# Mother_Board_ver2_0_0.net
KiCad netlist of a schematic drawn in EAGLE
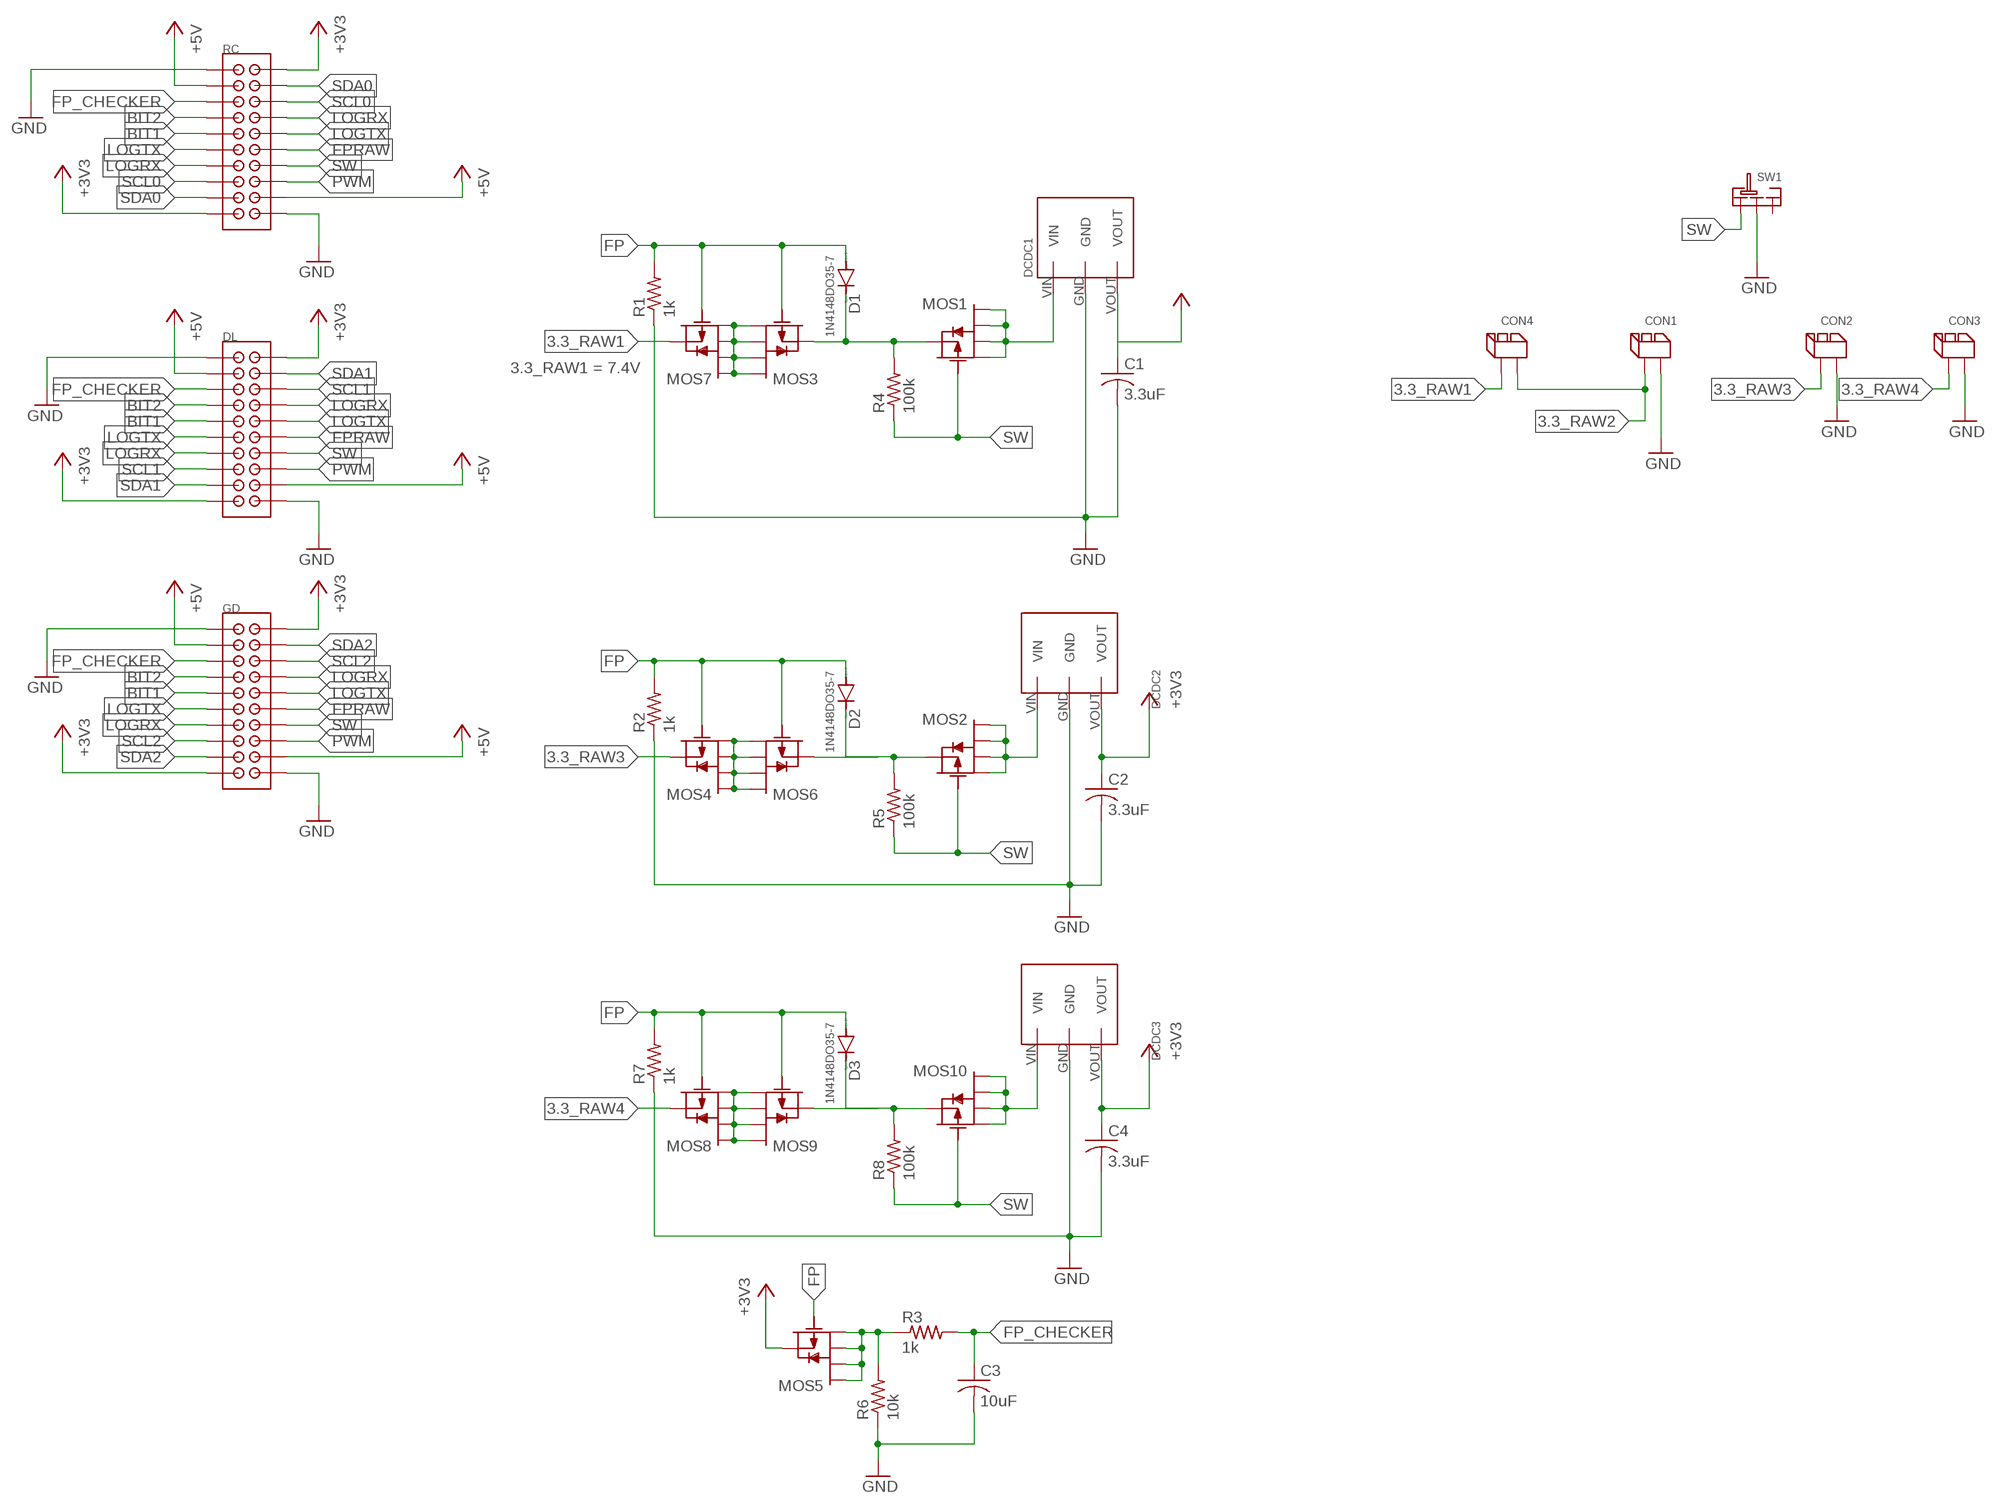
[diagram p0: schematic, sheet 1]

(export (version "E")
  (design (tool "Eeschema 10.0.6"))
  (components
    (comp (ref "C1")
      (value "3.3uF")
      (footprint "eagle-import:C0603")
      (libsource (lib "eagle-import") (part "C-USC0603"))
    )
    (comp (ref "C2")
      (value "3.3uF")
      (footprint "eagle-import:C0603")
      (libsource (lib "eagle-import") (part "C-USC0603"))
    )
    (comp (ref "C3")
      (value "10uF")
      (footprint "eagle-import:C0603")
      (libsource (lib "eagle-import") (part "C-USC0603"))
    )
    (comp (ref "C4")
      (value "3.3uF")
      (footprint "eagle-import:C0603")
      (libsource (lib "eagle-import") (part "C-USC0603"))
    )
    (comp (ref "CON1")
      (value "2PIN")
      (footprint "eagle-import:2PIN")
      (libsource (lib "eagle-import") (part "2PIN"))
    )
    (comp (ref "CON2")
      (value "2PIN")
      (footprint "eagle-import:2PIN")
      (libsource (lib "eagle-import") (part "2PIN"))
    )
    (comp (ref "CON3")
      (value "2PIN")
      (footprint "eagle-import:2PIN")
      (libsource (lib "eagle-import") (part "2PIN"))
    )
    (comp (ref "CON4")
      (value "2PIN")
      (footprint "eagle-import:2PIN")
      (libsource (lib "eagle-import") (part "2PIN"))
    )
    (comp (ref "D1")
      (value "1N4148DO35-7")
      (footprint "eagle-import:DO35-7")
      (libsource (lib "eagle-import") (part "1N4148DO35-7"))
    )
    (comp (ref "D2")
      (value "1N4148DO35-7")
      (footprint "eagle-import:DO35-7")
      (libsource (lib "eagle-import") (part "1N4148DO35-7"))
    )
    (comp (ref "D3")
      (value "1N4148DO35-7")
      (footprint "eagle-import:DO35-7")
      (libsource (lib "eagle-import") (part "1N4148DO35-7"))
    )
    (comp (ref "DCDC1")
      (value "5V1A_M78AR05-1")
      (footprint "eagle-import:5V1A_M78AR05-1")
      (libsource (lib "eagle-import") (part "5V1A_M78AR05-1"))
    )
    (comp (ref "DCDC2")
      (value "3.3V1A_M78AR033-1")
      (footprint "eagle-import:3.3V1A_M78AR033-1")
      (libsource (lib "eagle-import") (part "3.3V1A_M78AR033-1"))
    )
    (comp (ref "DCDC3")
      (value "3.3V1A_M78AR033-1")
      (footprint "eagle-import:3.3V1A_M78AR033-1")
      (libsource (lib "eagle-import") (part "3.3V1A_M78AR033-1"))
    )
    (comp (ref "DL")
      (value "2X10")
      (footprint "eagle-import:2X10")
      (libsource (lib "eagle-import") (part "2X10"))
    )
    (comp (ref "GD")
      (value "2X10")
      (footprint "eagle-import:2X10")
      (libsource (lib "eagle-import") (part "2X10"))
    )
    (comp (ref "MOS1")
      (value "PCH_SSM6J808R")
      (footprint "eagle-import:SSM6J808R")
      (libsource (lib "eagle-import") (part "PCH_SSM6J808R"))
    )
    (comp (ref "MOS2")
      (value "PCH_SSM6J808R")
      (footprint "eagle-import:SSM6J808R")
      (libsource (lib "eagle-import") (part "PCH_SSM6J808R"))
    )
    (comp (ref "MOS3")
      (value "PCH_SSM6J808R")
      (footprint "eagle-import:SSM6J808R")
      (libsource (lib "eagle-import") (part "PCH_SSM6J808R"))
    )
    (comp (ref "MOS4")
      (value "PCH_SSM6J808R")
      (footprint "eagle-import:SSM6J808R")
      (libsource (lib "eagle-import") (part "PCH_SSM6J808R"))
    )
    (comp (ref "MOS5")
      (value "PCH_SSM6J808R")
      (footprint "eagle-import:SSM6J808R")
      (libsource (lib "eagle-import") (part "PCH_SSM6J808R"))
    )
    (comp (ref "MOS6")
      (value "PCH_SSM6J808R")
      (footprint "eagle-import:SSM6J808R")
      (libsource (lib "eagle-import") (part "PCH_SSM6J808R"))
    )
    (comp (ref "MOS7")
      (value "PCH_SSM6J808R")
      (footprint "eagle-import:SSM6J808R")
      (libsource (lib "eagle-import") (part "PCH_SSM6J808R"))
    )
    (comp (ref "MOS8")
      (value "PCH_SSM6J808R")
      (footprint "eagle-import:SSM6J808R")
      (libsource (lib "eagle-import") (part "PCH_SSM6J808R"))
    )
    (comp (ref "MOS9")
      (value "PCH_SSM6J808R")
      (footprint "eagle-import:SSM6J808R")
      (libsource (lib "eagle-import") (part "PCH_SSM6J808R"))
    )
    (comp (ref "MOS10")
      (value "PCH_SSM6J808R")
      (footprint "eagle-import:SSM6J808R")
      (libsource (lib "eagle-import") (part "PCH_SSM6J808R"))
    )
    (comp (ref "R1")
      (value "1k")
      (footprint "eagle-import:R0603")
      (libsource (lib "eagle-import") (part "R-US_R0603"))
    )
    (comp (ref "R2")
      (value "1k")
      (footprint "eagle-import:R0603")
      (libsource (lib "eagle-import") (part "R-US_R0603"))
    )
    (comp (ref "R3")
      (value "1k")
      (footprint "eagle-import:R0603")
      (libsource (lib "eagle-import") (part "R-US_R0603"))
    )
    (comp (ref "R4")
      (value "100k")
      (footprint "eagle-import:R0603")
      (libsource (lib "eagle-import") (part "R-US_R0603"))
    )
    (comp (ref "R5")
      (value "100k")
      (footprint "eagle-import:R0603")
      (libsource (lib "eagle-import") (part "R-US_R0603"))
    )
    (comp (ref "R6")
      (value "10k")
      (footprint "eagle-import:R0603")
      (libsource (lib "eagle-import") (part "R-US_R0603"))
    )
    (comp (ref "R7")
      (value "1k")
      (footprint "eagle-import:R0603")
      (libsource (lib "eagle-import") (part "R-US_R0603"))
    )
    (comp (ref "R8")
      (value "100k")
      (footprint "eagle-import:R0603")
      (libsource (lib "eagle-import") (part "R-US_R0603"))
    )
    (comp (ref "RC")
      (value "2X10")
      (footprint "eagle-import:2X10")
      (libsource (lib "eagle-import") (part "2X10"))
    )
    (comp (ref "SW1")
      (value "SRIDE_SWITCH")
      (footprint "eagle-import:SRIDE_SWITCH")
      (libsource (lib "eagle-import") (part "SRIDE_SWITCH"))
    )
  )
  (nets
    (net (code "1") (name "+3V3") (class "Default")
      (node (ref "C2") (pin "1") (pinfunction "1_1") (pintype "passive"))
      (node (ref "C4") (pin "1") (pinfunction "1_1") (pintype "passive"))
      (node (ref "DCDC2") (pin "VOUT") (pinfunction "VOUT_VOUT") (pintype "bidirectional"))
      (node (ref "DCDC3") (pin "VOUT") (pinfunction "VOUT_VOUT") (pintype "bidirectional"))
      (node (ref "DL") (pin "P$19") (pinfunction "P$19_P$19") (pintype "bidirectional"))
      (node (ref "DL") (pin "P$2") (pinfunction "P$2_P$2") (pintype "bidirectional"))
      (node (ref "GD") (pin "P$19") (pinfunction "P$19_P$19") (pintype "bidirectional"))
      (node (ref "GD") (pin "P$2") (pinfunction "P$2_P$2") (pintype "bidirectional"))
      (node (ref "MOS5") (pin "4") (pinfunction "4_4") (pintype "bidirectional"))
      (node (ref "RC") (pin "P$19") (pinfunction "P$19_P$19") (pintype "bidirectional"))
      (node (ref "RC") (pin "P$2") (pinfunction "P$2_P$2") (pintype "bidirectional"))
    )
    (net (code "2") (name "+5V") (class "Default")
      (node (ref "C1") (pin "1") (pinfunction "1_1") (pintype "passive"))
      (node (ref "DCDC1") (pin "VOUT") (pinfunction "VOUT_VOUT") (pintype "bidirectional"))
      (node (ref "DL") (pin "P$18") (pinfunction "P$18_P$18") (pintype "bidirectional"))
      (node (ref "DL") (pin "P$3") (pinfunction "P$3_P$3") (pintype "bidirectional"))
      (node (ref "GD") (pin "P$18") (pinfunction "P$18_P$18") (pintype "bidirectional"))
      (node (ref "GD") (pin "P$3") (pinfunction "P$3_P$3") (pintype "bidirectional"))
      (node (ref "RC") (pin "P$18") (pinfunction "P$18_P$18") (pintype "bidirectional"))
      (node (ref "RC") (pin "P$3") (pinfunction "P$3_P$3") (pintype "bidirectional"))
    )
    (net (code "3") (name "3.3_RAW1") (class "Default")
      (node (ref "CON4") (pin "P$2") (pinfunction "P$2_P$2") (pintype "bidirectional"))
      (node (ref "MOS7") (pin "4") (pinfunction "4_4") (pintype "bidirectional"))
    )
    (net (code "4") (name "3.3_RAW2") (class "Default")
      (node (ref "CON1") (pin "P$2") (pinfunction "P$2_P$2") (pintype "bidirectional"))
      (node (ref "CON4") (pin "P$1") (pinfunction "P$1_P$1") (pintype "bidirectional"))
    )
    (net (code "5") (name "3.3_RAW3") (class "Default")
      (node (ref "CON2") (pin "P$2") (pinfunction "P$2_P$2") (pintype "bidirectional"))
      (node (ref "MOS4") (pin "4") (pinfunction "4_4") (pintype "bidirectional"))
    )
    (net (code "6") (name "3.3_RAW4") (class "Default")
      (node (ref "CON3") (pin "P$2") (pinfunction "P$2_P$2") (pintype "bidirectional"))
      (node (ref "MOS8") (pin "4") (pinfunction "4_4") (pintype "bidirectional"))
    )
    (net (code "7") (name "BIT1") (class "Default")
      (node (ref "DL") (pin "P$9") (pinfunction "P$9_P$9") (pintype "bidirectional"))
      (node (ref "GD") (pin "P$9") (pinfunction "P$9_P$9") (pintype "bidirectional"))
      (node (ref "RC") (pin "P$9") (pinfunction "P$9_P$9") (pintype "bidirectional"))
    )
    (net (code "8") (name "BIT2") (class "Default")
      (node (ref "DL") (pin "P$7") (pinfunction "P$7_P$7") (pintype "bidirectional"))
      (node (ref "GD") (pin "P$7") (pinfunction "P$7_P$7") (pintype "bidirectional"))
      (node (ref "RC") (pin "P$7") (pinfunction "P$7_P$7") (pintype "bidirectional"))
    )
    (net (code "9") (name "FP") (class "Default")
      (node (ref "D1") (pin "A") (pinfunction "A_A") (pintype "passive"))
      (node (ref "D2") (pin "A") (pinfunction "A_A") (pintype "passive"))
      (node (ref "D3") (pin "A") (pinfunction "A_A") (pintype "passive"))
      (node (ref "MOS3") (pin "3") (pinfunction "3_3") (pintype "bidirectional"))
      (node (ref "MOS4") (pin "3") (pinfunction "3_3") (pintype "bidirectional"))
      (node (ref "MOS5") (pin "3") (pinfunction "3_3") (pintype "bidirectional"))
      (node (ref "MOS6") (pin "3") (pinfunction "3_3") (pintype "bidirectional"))
      (node (ref "MOS7") (pin "3") (pinfunction "3_3") (pintype "bidirectional"))
      (node (ref "MOS8") (pin "3") (pinfunction "3_3") (pintype "bidirectional"))
      (node (ref "MOS9") (pin "3") (pinfunction "3_3") (pintype "bidirectional"))
      (node (ref "R1") (pin "2") (pinfunction "2_2") (pintype "passive"))
      (node (ref "R2") (pin "2") (pinfunction "2_2") (pintype "passive"))
      (node (ref "R7") (pin "2") (pinfunction "2_2") (pintype "passive"))
    )
    (net (code "10") (name "FPRAW") (class "Default")
      (node (ref "DL") (pin "P$12") (pinfunction "P$12_P$12") (pintype "bidirectional"))
      (node (ref "GD") (pin "P$12") (pinfunction "P$12_P$12") (pintype "bidirectional"))
      (node (ref "RC") (pin "P$12") (pinfunction "P$12_P$12") (pintype "bidirectional"))
    )
    (net (code "11") (name "FP_CHECKER") (class "Default")
      (node (ref "C3") (pin "1") (pinfunction "1_1") (pintype "passive"))
      (node (ref "DL") (pin "P$5") (pinfunction "P$5_P$5") (pintype "bidirectional"))
      (node (ref "GD") (pin "P$5") (pinfunction "P$5_P$5") (pintype "bidirectional"))
      (node (ref "R3") (pin "2") (pinfunction "2_2") (pintype "passive"))
      (node (ref "RC") (pin "P$5") (pinfunction "P$5_P$5") (pintype "bidirectional"))
    )
    (net (code "12") (name "GND") (class "Default")
      (node (ref "C1") (pin "2") (pinfunction "2_2") (pintype "passive"))
      (node (ref "C2") (pin "2") (pinfunction "2_2") (pintype "passive"))
      (node (ref "C3") (pin "2") (pinfunction "2_2") (pintype "passive"))
      (node (ref "C4") (pin "2") (pinfunction "2_2") (pintype "passive"))
      (node (ref "CON1") (pin "P$1") (pinfunction "P$1_P$1") (pintype "bidirectional"))
      (node (ref "CON2") (pin "P$1") (pinfunction "P$1_P$1") (pintype "bidirectional"))
      (node (ref "CON3") (pin "P$1") (pinfunction "P$1_P$1") (pintype "bidirectional"))
      (node (ref "DCDC1") (pin "GND") (pinfunction "GND_GND") (pintype "bidirectional"))
      (node (ref "DCDC2") (pin "GND") (pinfunction "GND_GND") (pintype "bidirectional"))
      (node (ref "DCDC3") (pin "GND") (pinfunction "GND_GND") (pintype "bidirectional"))
      (node (ref "DL") (pin "P$1") (pinfunction "P$1_P$1") (pintype "bidirectional"))
      (node (ref "DL") (pin "P$20") (pinfunction "P$20_P$20") (pintype "bidirectional"))
      (node (ref "GD") (pin "P$1") (pinfunction "P$1_P$1") (pintype "bidirectional"))
      (node (ref "GD") (pin "P$20") (pinfunction "P$20_P$20") (pintype "bidirectional"))
      (node (ref "R1") (pin "1") (pinfunction "1_1") (pintype "passive"))
      (node (ref "R2") (pin "1") (pinfunction "1_1") (pintype "passive"))
      (node (ref "R6") (pin "1") (pinfunction "1_1") (pintype "passive"))
      (node (ref "R7") (pin "1") (pinfunction "1_1") (pintype "passive"))
      (node (ref "RC") (pin "P$1") (pinfunction "P$1_P$1") (pintype "bidirectional"))
      (node (ref "RC") (pin "P$20") (pinfunction "P$20_P$20") (pintype "bidirectional"))
      (node (ref "SW1") (pin "LR") (pinfunction "LR_LR") (pintype "bidirectional"))
    )
    (net (code "13") (name "LOGRX") (class "Default")
      (node (ref "DL") (pin "P$13") (pinfunction "P$13_P$13") (pintype "bidirectional"))
      (node (ref "DL") (pin "P$8") (pinfunction "P$8_P$8") (pintype "bidirectional"))
      (node (ref "GD") (pin "P$13") (pinfunction "P$13_P$13") (pintype "bidirectional"))
      (node (ref "GD") (pin "P$8") (pinfunction "P$8_P$8") (pintype "bidirectional"))
      (node (ref "RC") (pin "P$13") (pinfunction "P$13_P$13") (pintype "bidirectional"))
      (node (ref "RC") (pin "P$8") (pinfunction "P$8_P$8") (pintype "bidirectional"))
    )
    (net (code "14") (name "LOGTX") (class "Default")
      (node (ref "DL") (pin "P$10") (pinfunction "P$10_P$10") (pintype "bidirectional"))
      (node (ref "DL") (pin "P$11") (pinfunction "P$11_P$11") (pintype "bidirectional"))
      (node (ref "GD") (pin "P$10") (pinfunction "P$10_P$10") (pintype "bidirectional"))
      (node (ref "GD") (pin "P$11") (pinfunction "P$11_P$11") (pintype "bidirectional"))
      (node (ref "RC") (pin "P$10") (pinfunction "P$10_P$10") (pintype "bidirectional"))
      (node (ref "RC") (pin "P$11") (pinfunction "P$11_P$11") (pintype "bidirectional"))
    )
    (net (code "15") (name "Net-(D1-PadC)") (class "Default")
      (node (ref "D1") (pin "C") (pinfunction "C_C") (pintype "passive"))
      (node (ref "MOS1") (pin "4") (pinfunction "4_4") (pintype "bidirectional"))
      (node (ref "MOS3") (pin "4") (pinfunction "4_4") (pintype "bidirectional"))
      (node (ref "R4") (pin "2") (pinfunction "2_2") (pintype "passive"))
    )
    (net (code "16") (name "Net-(D2-PadC)") (class "Default")
      (node (ref "D2") (pin "C") (pinfunction "C_C") (pintype "passive"))
      (node (ref "MOS2") (pin "4") (pinfunction "4_4") (pintype "bidirectional"))
      (node (ref "MOS6") (pin "4") (pinfunction "4_4") (pintype "bidirectional"))
      (node (ref "R5") (pin "2") (pinfunction "2_2") (pintype "passive"))
    )
    (net (code "17") (name "Net-(D3-PadC)") (class "Default")
      (node (ref "D3") (pin "C") (pinfunction "C_C") (pintype "passive"))
      (node (ref "MOS10") (pin "4") (pinfunction "4_4") (pintype "bidirectional"))
      (node (ref "MOS9") (pin "4") (pinfunction "4_4") (pintype "bidirectional"))
      (node (ref "R8") (pin "2") (pinfunction "2_2") (pintype "passive"))
    )
    (net (code "18") (name "Net-(DCDC1-PadVIN)") (class "Default")
      (node (ref "DCDC1") (pin "VIN") (pinfunction "VIN_VIN") (pintype "bidirectional"))
      (node (ref "MOS1") (pin "1") (pinfunction "1_1") (pintype "bidirectional"))
      (node (ref "MOS1") (pin "2") (pinfunction "2_2") (pintype "bidirectional"))
      (node (ref "MOS1") (pin "5") (pinfunction "5_5") (pintype "bidirectional"))
      (node (ref "MOS1") (pin "6") (pinfunction "6_6") (pintype "bidirectional"))
    )
    (net (code "19") (name "Net-(DCDC2-PadVIN)") (class "Default")
      (node (ref "DCDC2") (pin "VIN") (pinfunction "VIN_VIN") (pintype "bidirectional"))
      (node (ref "MOS2") (pin "1") (pinfunction "1_1") (pintype "bidirectional"))
      (node (ref "MOS2") (pin "2") (pinfunction "2_2") (pintype "bidirectional"))
      (node (ref "MOS2") (pin "5") (pinfunction "5_5") (pintype "bidirectional"))
      (node (ref "MOS2") (pin "6") (pinfunction "6_6") (pintype "bidirectional"))
    )
    (net (code "20") (name "Net-(DCDC3-PadVIN)") (class "Default")
      (node (ref "DCDC3") (pin "VIN") (pinfunction "VIN_VIN") (pintype "bidirectional"))
      (node (ref "MOS10") (pin "1") (pinfunction "1_1") (pintype "bidirectional"))
      (node (ref "MOS10") (pin "2") (pinfunction "2_2") (pintype "bidirectional"))
      (node (ref "MOS10") (pin "5") (pinfunction "5_5") (pintype "bidirectional"))
      (node (ref "MOS10") (pin "6") (pinfunction "6_6") (pintype "bidirectional"))
    )
    (net (code "21") (name "Net-(MOS3-Pad1)") (class "Default")
      (node (ref "MOS3") (pin "1") (pinfunction "1_1") (pintype "bidirectional"))
      (node (ref "MOS3") (pin "2") (pinfunction "2_2") (pintype "bidirectional"))
      (node (ref "MOS3") (pin "5") (pinfunction "5_5") (pintype "bidirectional"))
      (node (ref "MOS3") (pin "6") (pinfunction "6_6") (pintype "bidirectional"))
      (node (ref "MOS7") (pin "1") (pinfunction "1_1") (pintype "bidirectional"))
      (node (ref "MOS7") (pin "2") (pinfunction "2_2") (pintype "bidirectional"))
      (node (ref "MOS7") (pin "5") (pinfunction "5_5") (pintype "bidirectional"))
      (node (ref "MOS7") (pin "6") (pinfunction "6_6") (pintype "bidirectional"))
    )
    (net (code "22") (name "Net-(MOS4-Pad1)") (class "Default")
      (node (ref "MOS4") (pin "1") (pinfunction "1_1") (pintype "bidirectional"))
      (node (ref "MOS4") (pin "2") (pinfunction "2_2") (pintype "bidirectional"))
      (node (ref "MOS4") (pin "5") (pinfunction "5_5") (pintype "bidirectional"))
      (node (ref "MOS4") (pin "6") (pinfunction "6_6") (pintype "bidirectional"))
      (node (ref "MOS6") (pin "1") (pinfunction "1_1") (pintype "bidirectional"))
      (node (ref "MOS6") (pin "2") (pinfunction "2_2") (pintype "bidirectional"))
      (node (ref "MOS6") (pin "5") (pinfunction "5_5") (pintype "bidirectional"))
      (node (ref "MOS6") (pin "6") (pinfunction "6_6") (pintype "bidirectional"))
    )
    (net (code "23") (name "Net-(MOS5-Pad1)") (class "Default")
      (node (ref "MOS5") (pin "1") (pinfunction "1_1") (pintype "bidirectional"))
      (node (ref "MOS5") (pin "2") (pinfunction "2_2") (pintype "bidirectional"))
      (node (ref "MOS5") (pin "5") (pinfunction "5_5") (pintype "bidirectional"))
      (node (ref "MOS5") (pin "6") (pinfunction "6_6") (pintype "bidirectional"))
      (node (ref "R3") (pin "1") (pinfunction "1_1") (pintype "passive"))
      (node (ref "R6") (pin "2") (pinfunction "2_2") (pintype "passive"))
    )
    (net (code "24") (name "Net-(MOS8-Pad1)") (class "Default")
      (node (ref "MOS8") (pin "1") (pinfunction "1_1") (pintype "bidirectional"))
      (node (ref "MOS8") (pin "2") (pinfunction "2_2") (pintype "bidirectional"))
      (node (ref "MOS8") (pin "5") (pinfunction "5_5") (pintype "bidirectional"))
      (node (ref "MOS8") (pin "6") (pinfunction "6_6") (pintype "bidirectional"))
      (node (ref "MOS9") (pin "1") (pinfunction "1_1") (pintype "bidirectional"))
      (node (ref "MOS9") (pin "2") (pinfunction "2_2") (pintype "bidirectional"))
      (node (ref "MOS9") (pin "5") (pinfunction "5_5") (pintype "bidirectional"))
      (node (ref "MOS9") (pin "6") (pinfunction "6_6") (pintype "bidirectional"))
    )
    (net (code "25") (name "PWM") (class "Default")
      (node (ref "DL") (pin "P$16") (pinfunction "P$16_P$16") (pintype "bidirectional"))
      (node (ref "GD") (pin "P$16") (pinfunction "P$16_P$16") (pintype "bidirectional"))
      (node (ref "RC") (pin "P$16") (pinfunction "P$16_P$16") (pintype "bidirectional"))
    )
    (net (code "26") (name "SCL0") (class "Default")
      (node (ref "RC") (pin "P$15") (pinfunction "P$15_P$15") (pintype "bidirectional"))
      (node (ref "RC") (pin "P$6") (pinfunction "P$6_P$6") (pintype "bidirectional"))
    )
    (net (code "27") (name "SCL1") (class "Default")
      (node (ref "DL") (pin "P$15") (pinfunction "P$15_P$15") (pintype "bidirectional"))
      (node (ref "DL") (pin "P$6") (pinfunction "P$6_P$6") (pintype "bidirectional"))
    )
    (net (code "28") (name "SCL2") (class "Default")
      (node (ref "GD") (pin "P$15") (pinfunction "P$15_P$15") (pintype "bidirectional"))
      (node (ref "GD") (pin "P$6") (pinfunction "P$6_P$6") (pintype "bidirectional"))
    )
    (net (code "29") (name "SDA0") (class "Default")
      (node (ref "RC") (pin "P$17") (pinfunction "P$17_P$17") (pintype "bidirectional"))
      (node (ref "RC") (pin "P$4") (pinfunction "P$4_P$4") (pintype "bidirectional"))
    )
    (net (code "30") (name "SDA1") (class "Default")
      (node (ref "DL") (pin "P$17") (pinfunction "P$17_P$17") (pintype "bidirectional"))
      (node (ref "DL") (pin "P$4") (pinfunction "P$4_P$4") (pintype "bidirectional"))
    )
    (net (code "31") (name "SDA2") (class "Default")
      (node (ref "GD") (pin "P$17") (pinfunction "P$17_P$17") (pintype "bidirectional"))
      (node (ref "GD") (pin "P$4") (pinfunction "P$4_P$4") (pintype "bidirectional"))
    )
    (net (code "32") (name "SW") (class "Default")
      (node (ref "DL") (pin "P$14") (pinfunction "P$14_P$14") (pintype "bidirectional"))
      (node (ref "GD") (pin "P$14") (pinfunction "P$14_P$14") (pintype "bidirectional"))
      (node (ref "MOS1") (pin "3") (pinfunction "3_3") (pintype "bidirectional"))
      (node (ref "MOS10") (pin "3") (pinfunction "3_3") (pintype "bidirectional"))
      (node (ref "MOS2") (pin "3") (pinfunction "3_3") (pintype "bidirectional"))
      (node (ref "R4") (pin "1") (pinfunction "1_1") (pintype "passive"))
      (node (ref "R5") (pin "1") (pinfunction "1_1") (pintype "passive"))
      (node (ref "R8") (pin "1") (pinfunction "1_1") (pintype "passive"))
      (node (ref "RC") (pin "P$14") (pinfunction "P$14_P$14") (pintype "bidirectional"))
      (node (ref "SW1") (pin "L") (pinfunction "L_L") (pintype "bidirectional"))
    )
    (net (code "33") (name "unconnected-(SW1-PadR)") (class "Default")
      (node (ref "SW1") (pin "R") (pinfunction "R_R") (pintype "bidirectional"))
    )
  )
)
